# RJ_IGVC_Estop.net
KiCad netlist of a schematic drawn in EAGLE
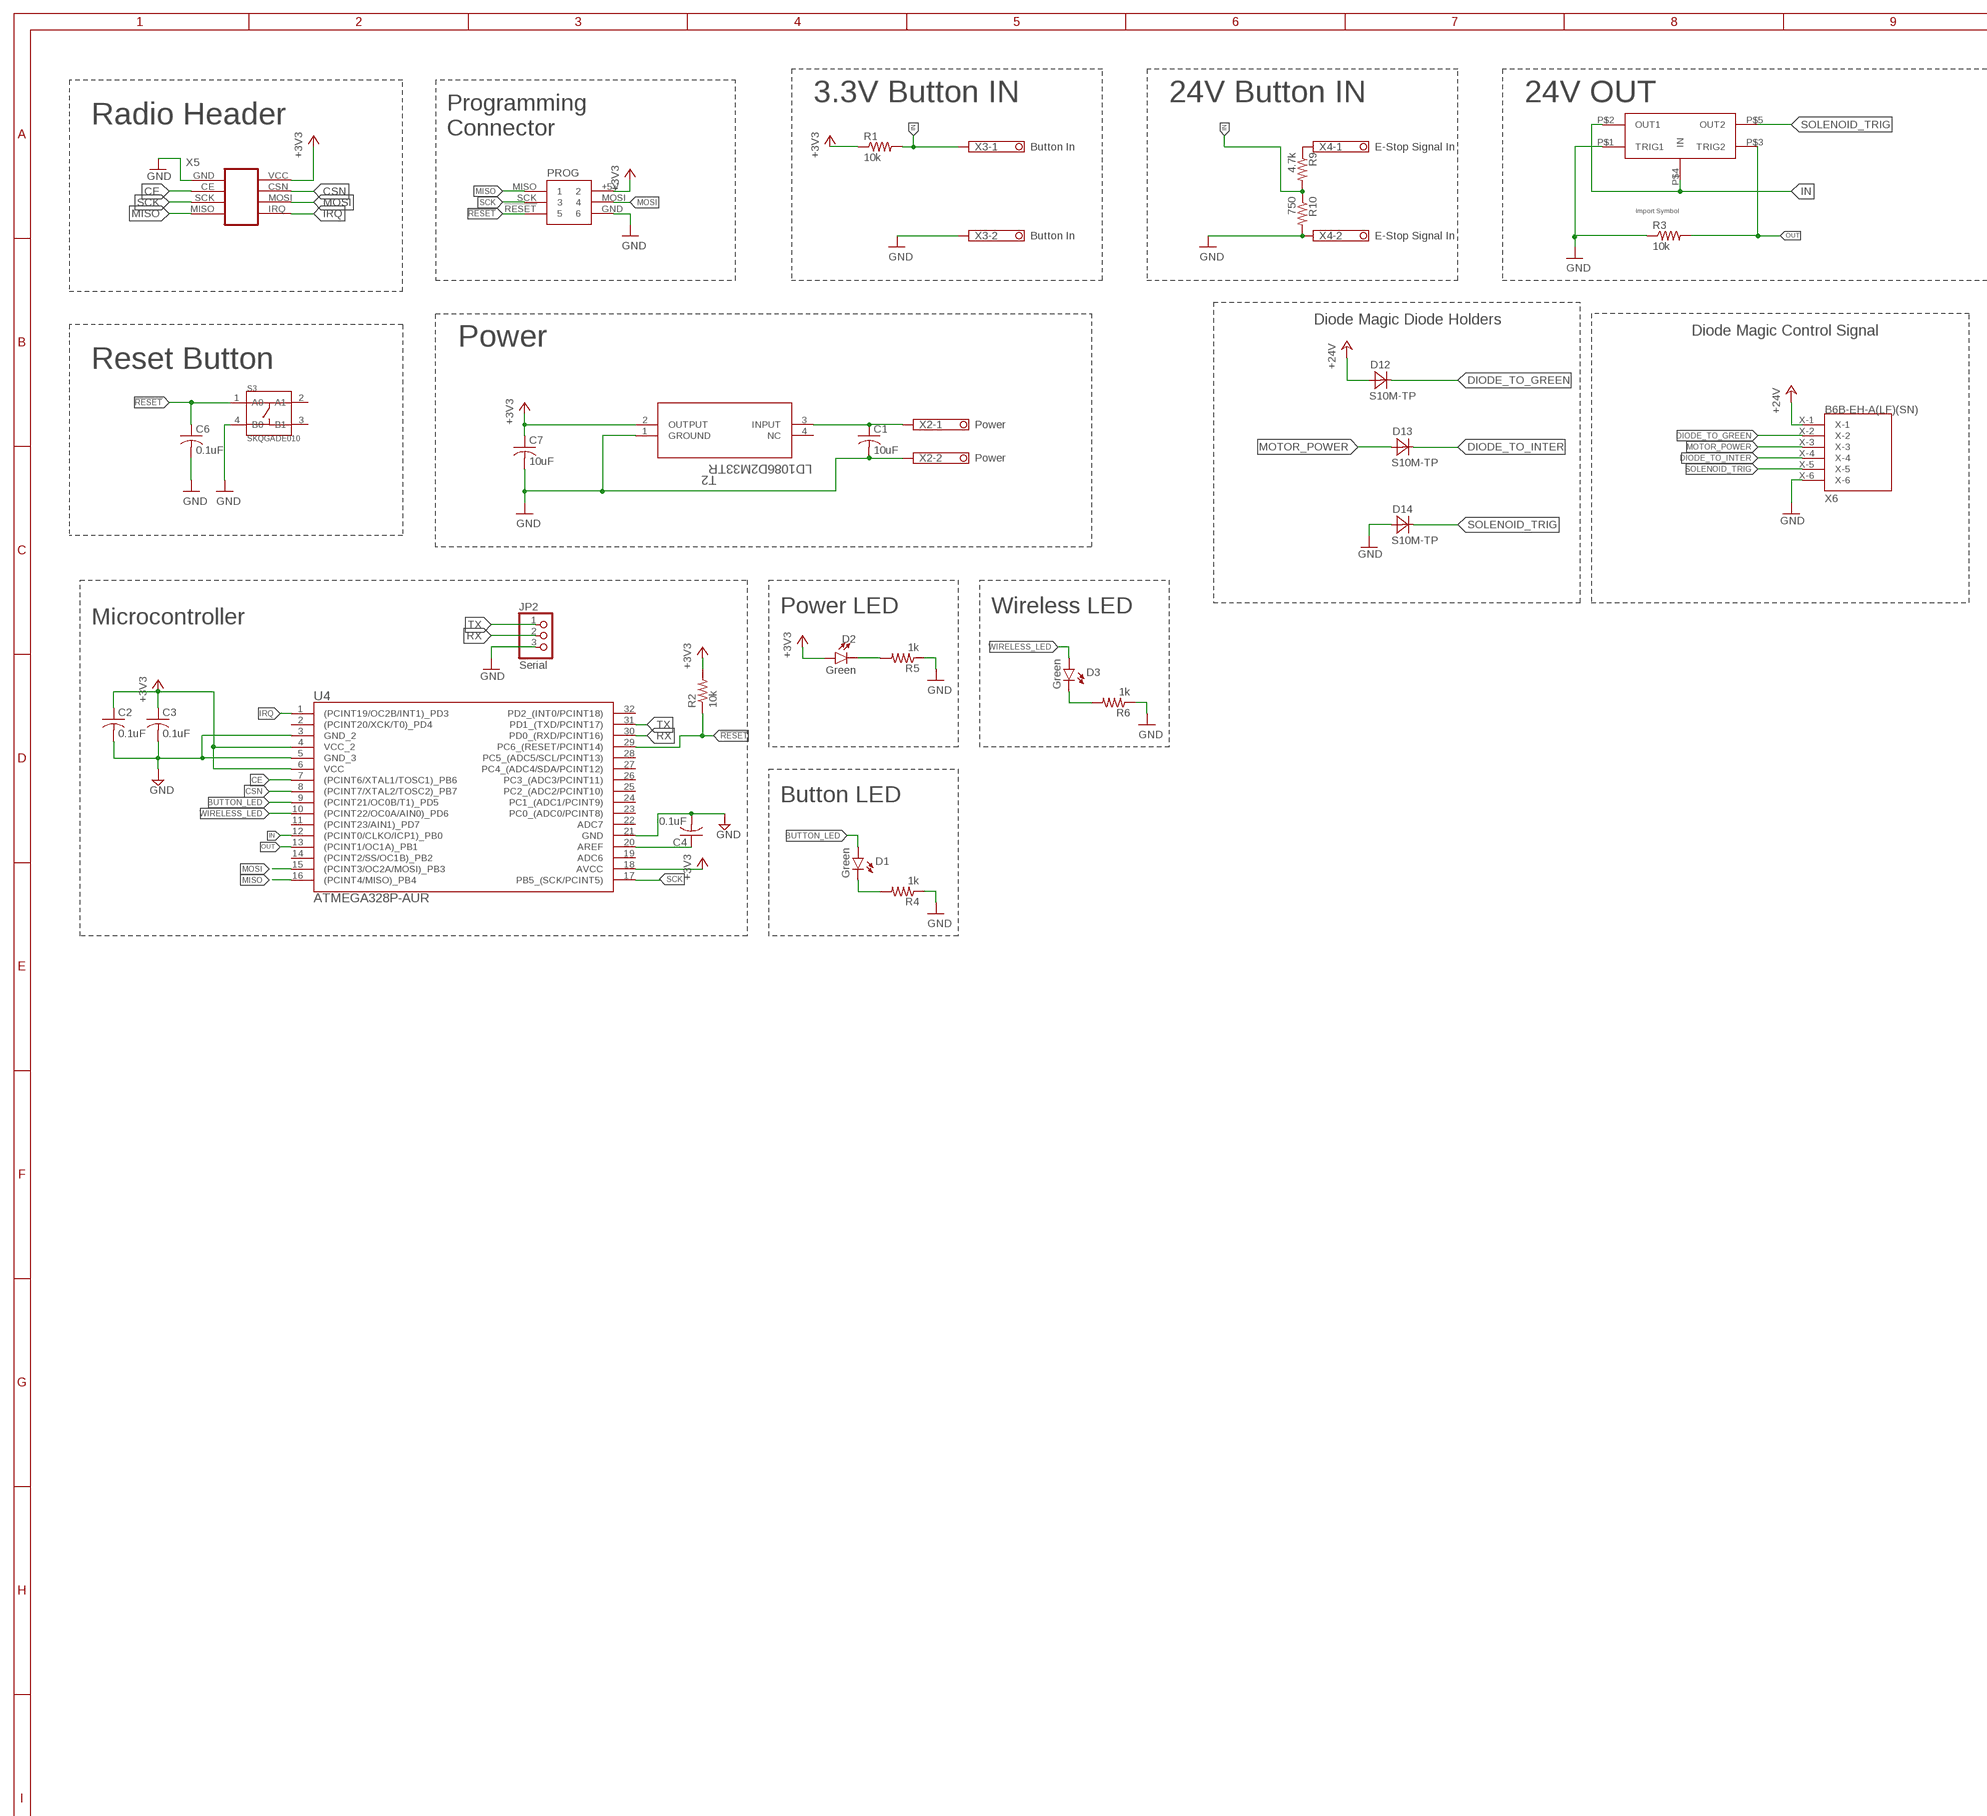
[diagram p0: schematic, sheet 1, part 1 of 2]
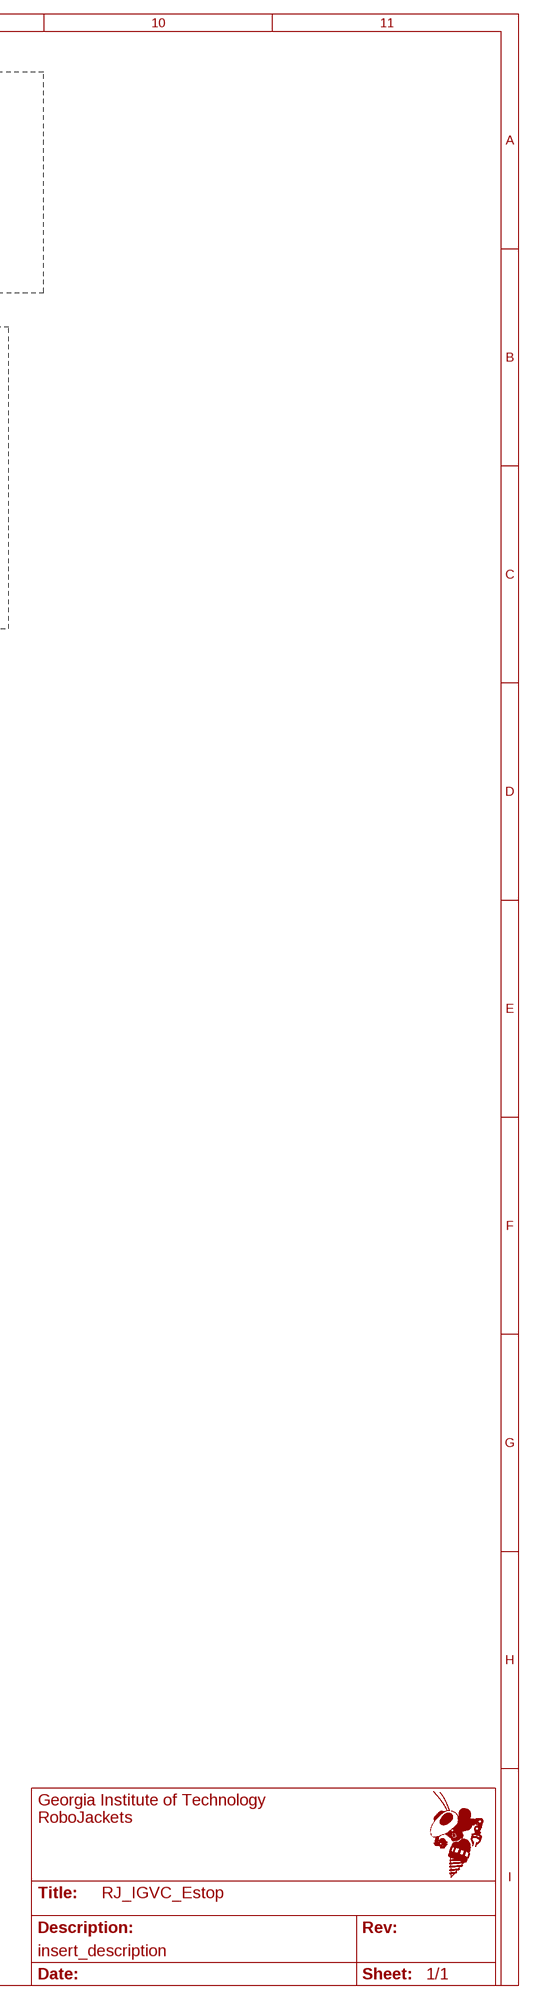
[diagram p1: schematic, sheet 1, part 2 of 2]

(export (version "E")
  (design (tool "Eeschema 10.0.6"))
  (components
    (comp (ref "C1")
      (value "10uF")
      (footprint "eagle-import:C1206")
      (libsource (lib "eagle-import") (part "C-USC1206"))
    )
    (comp (ref "C2")
      (value "0.1uF")
      (footprint "eagle-import:C0603")
      (libsource (lib "eagle-import") (part "C-USC0603"))
    )
    (comp (ref "C3")
      (value "0.1uF")
      (footprint "eagle-import:C0603")
      (libsource (lib "eagle-import") (part "C-USC0603"))
    )
    (comp (ref "C4")
      (value "0.1uF")
      (footprint "eagle-import:C0603")
      (libsource (lib "eagle-import") (part "C-USC0603"))
    )
    (comp (ref "C6")
      (value "0.1uF")
      (footprint "eagle-import:C0603")
      (libsource (lib "eagle-import") (part "resistor_348_C-USC0603"))
    )
    (comp (ref "C7")
      (value "10uF")
      (footprint "eagle-import:C1206")
      (libsource (lib "eagle-import") (part "C-USC1206"))
    )
    (comp (ref "D1")
      (value "Green")
      (footprint "eagle-import:LED-0603")
      (libsource (lib "eagle-import") (part "LED-YELLOW0603"))
    )
    (comp (ref "D2")
      (value "Green")
      (footprint "eagle-import:LED-0603")
      (libsource (lib "eagle-import") (part "LED-YELLOW0603"))
    )
    (comp (ref "D3")
      (value "Green")
      (footprint "eagle-import:LED-0603")
      (libsource (lib "eagle-import") (part "LED-YELLOW0603"))
    )
    (comp (ref "D12")
      (value "S10M-TP")
      (footprint "eagle-import:SMC")
      (libsource (lib "eagle-import") (part "S10M-TP"))
    )
    (comp (ref "D13")
      (value "S10M-TP")
      (footprint "eagle-import:SMC")
      (libsource (lib "eagle-import") (part "S10M-TP"))
    )
    (comp (ref "D14")
      (value "S10M-TP")
      (footprint "eagle-import:SMC")
      (libsource (lib "eagle-import") (part "S10M-TP"))
    )
    (comp (ref "JP2")
      (value "Serial")
      (footprint "eagle-import:1X03")
      (libsource (lib "eagle-import") (part "PINHD-1X3"))
    )
    (comp (ref "PROG")
      (value "ICSP Connector")
      (footprint "eagle-import:2X3SHROUDED")
      (libsource (lib "eagle-import") (part "2X3SHROUDED"))
    )
    (comp (ref "R1")
      (value "10k")
      (footprint "eagle-import:R0603")
      (libsource (lib "eagle-import") (part "resistor_348_R-US_R0603"))
    )
    (comp (ref "R2")
      (value "10k")
      (footprint "eagle-import:R0603")
      (libsource (lib "eagle-import") (part "R-US_R0603"))
    )
    (comp (ref "R3")
      (value "10k")
      (footprint "eagle-import:R0603")
      (libsource (lib "eagle-import") (part "resistor_348_R-US_R0603"))
    )
    (comp (ref "R4")
      (value "1k")
      (footprint "eagle-import:R0603")
      (libsource (lib "eagle-import") (part "resistor_348_R-US_R0603"))
    )
    (comp (ref "R5")
      (value "1k")
      (footprint "eagle-import:R0603")
      (libsource (lib "eagle-import") (part "resistor_348_R-US_R0603"))
    )
    (comp (ref "R6")
      (value "1k")
      (footprint "eagle-import:R0603")
      (libsource (lib "eagle-import") (part "resistor_348_R-US_R0603"))
    )
    (comp (ref "R9")
      (value "4.7k")
      (footprint "eagle-import:R0603")
      (libsource (lib "eagle-import") (part "resistor_348_R-US_R0603"))
    )
    (comp (ref "R10")
      (value "750")
      (footprint "eagle-import:R0603")
      (libsource (lib "eagle-import") (part "resistor_348_R-US_R0603"))
    )
    (comp (ref "S3")
      (value "SKQGADE010")
      (footprint "eagle-import:SW4-SMD-5.2X5.2X1.5MM")
      (libsource (lib "eagle-import") (part "SMD-SWITCH-TOP-260GF(4P-D5.2MM)"))
    )
    (comp (ref "T2")
      (value "LD1086D2M33TR")
      (footprint "eagle-import:D2PAK_A")
      (libsource (lib "eagle-import") (part "LD1086D2M33TR"))
    )
    (comp (ref "U$1")
      (value "G5LE-14")
      (footprint "eagle-import:G5LE-14")
      (libsource (lib "eagle-import") (part "G5LE-14"))
    )
    (comp (ref "U4")
      (value "ATMEGA328P-AUR")
      (footprint "eagle-import:ATMEGA328P-AUR")
      (libsource (lib "eagle-import") (part "ATMEGA328P-AUR"))
    )
    (comp (ref "X2")
      (value "Power")
      (footprint "eagle-import:1751248")
      (libsource (lib "eagle-import") (part "1751248"))
    )
    (comp (ref "X3")
      (value "Button In")
      (footprint "eagle-import:1751248")
      (libsource (lib "eagle-import") (part "1751248"))
    )
    (comp (ref "X4")
      (value "E-Stop Signal In")
      (footprint "eagle-import:1751248")
      (libsource (lib "eagle-import") (part "1751248"))
    )
    (comp (ref "X5")
      (value "NRF24L01+PA+LNA")
      (footprint "eagle-import:NRF24L01+PA+LNA")
      (libsource (lib "eagle-import") (part "NRF24L01+PA+LNA"))
    )
    (comp (ref "X6")
      (value "B6B-EH-A(LF)(SN)")
      (footprint "eagle-import:B6BEHALFSN")
      (libsource (lib "eagle-import") (part "B6B-EH-A(LF)(SN)"))
    )
  )
  (nets
    (net (code "1") (name "+3V3") (class "Default")
      (node (ref "C2") (pin "1") (pinfunction "1_1") (pintype "passive"))
      (node (ref "C3") (pin "1") (pinfunction "1_1") (pintype "passive"))
      (node (ref "C7") (pin "1") (pinfunction "1_1") (pintype "passive"))
      (node (ref "D2") (pin "A") (pinfunction "A_A") (pintype "passive"))
      (node (ref "PROG") (pin "+5V") (pinfunction "2_+5V") (pintype "bidirectional"))
      (node (ref "R1") (pin "1") (pinfunction "1_1") (pintype "passive"))
      (node (ref "R2") (pin "2") (pinfunction "2_2") (pintype "passive"))
      (node (ref "T2") (pin "2") (pinfunction "OUTPUT_2") (pintype "passive"))
      (node (ref "U4") (pin "18") (pinfunction "AVCC_18") (pintype "bidirectional"))
      (node (ref "U4") (pin "4") (pinfunction "VCC_2_4") (pintype "bidirectional"))
      (node (ref "U4") (pin "6") (pinfunction "VCC_6") (pintype "bidirectional"))
      (node (ref "X5") (pin "VCC") (pinfunction "VCC_VCC") (pintype "power_in"))
    )
    (net (code "2") (name "+24V") (class "Default")
      (node (ref "D12") (pin "A") (pinfunction "A_A") (pintype "passive"))
      (node (ref "X6") (pin "X-1") (pinfunction "X-1_X-1") (pintype "bidirectional"))
    )
    (net (code "3") (name "/~{RESET}") (class "Default")
      (node (ref "C6") (pin "1") (pinfunction "1_1") (pintype "passive"))
      (node (ref "PROG") (pin "!RESET") (pinfunction "5_!RESET") (pintype "bidirectional"))
      (node (ref "R2") (pin "1") (pinfunction "1_1") (pintype "passive"))
      (node (ref "S3") (pin "1") (pinfunction "A0_1") (pintype "bidirectional"))
      (node (ref "U4") (pin "29") (pinfunction "PC6_(RESET/PCINT14)_29") (pintype "bidirectional"))
    )
    (net (code "4") (name "BUTTON_LED") (class "Default")
      (node (ref "D1") (pin "A") (pinfunction "A_A") (pintype "passive"))
      (node (ref "U4") (pin "9") (pinfunction "(PCINT21/OC0B/T1)_PD5_9") (pintype "bidirectional"))
    )
    (net (code "5") (name "CE") (class "Default")
      (node (ref "U4") (pin "7") (pinfunction "(PCINT6/XTAL1/TOSC1)_PB6_7") (pintype "bidirectional"))
      (node (ref "X5") (pin "CE") (pinfunction "CE_CE") (pintype "passive"))
    )
    (net (code "6") (name "CSN") (class "Default")
      (node (ref "U4") (pin "8") (pinfunction "(PCINT7/XTAL2/TOSC2)_PB7_8") (pintype "bidirectional"))
      (node (ref "X5") (pin "CSN") (pinfunction "CSN_CSN") (pintype "passive"))
    )
    (net (code "7") (name "DIODE_TO_GREEN") (class "Default")
      (node (ref "D12") (pin "C") (pinfunction "C_C") (pintype "passive"))
      (node (ref "X6") (pin "X-2") (pinfunction "X-2_X-2") (pintype "bidirectional"))
    )
    (net (code "8") (name "DIODE_TO_INTER") (class "Default")
      (node (ref "D13") (pin "C") (pinfunction "C_C") (pintype "passive"))
      (node (ref "X6") (pin "X-4") (pinfunction "X-4_X-4") (pintype "bidirectional"))
    )
    (net (code "9") (name "GND") (class "Default")
      (node (ref "C1") (pin "2") (pinfunction "2_2") (pintype "passive"))
      (node (ref "C2") (pin "2") (pinfunction "2_2") (pintype "passive"))
      (node (ref "C3") (pin "2") (pinfunction "2_2") (pintype "passive"))
      (node (ref "C4") (pin "2") (pinfunction "2_2") (pintype "passive"))
      (node (ref "C6") (pin "2") (pinfunction "2_2") (pintype "passive"))
      (node (ref "C7") (pin "2") (pinfunction "2_2") (pintype "passive"))
      (node (ref "D14") (pin "A") (pinfunction "A_A") (pintype "passive"))
      (node (ref "JP2") (pin "3") (pinfunction "3_3") (pintype "passive"))
      (node (ref "PROG") (pin "GND") (pinfunction "6_GND") (pintype "bidirectional"))
      (node (ref "R10") (pin "2") (pinfunction "2_2") (pintype "passive"))
      (node (ref "R3") (pin "1") (pinfunction "1_1") (pintype "passive"))
      (node (ref "R4") (pin "1") (pinfunction "1_1") (pintype "passive"))
      (node (ref "R5") (pin "1") (pinfunction "1_1") (pintype "passive"))
      (node (ref "R6") (pin "1") (pinfunction "1_1") (pintype "passive"))
      (node (ref "S3") (pin "4") (pinfunction "B0_4") (pintype "bidirectional"))
      (node (ref "T2") (pin "1") (pinfunction "GROUND_1") (pintype "passive"))
      (node (ref "U$1") (pin "P$1") (pinfunction "TRIG1_P$1") (pintype "bidirectional"))
      (node (ref "U4") (pin "21") (pinfunction "GND_21") (pintype "bidirectional"))
      (node (ref "U4") (pin "3") (pinfunction "GND_2_3") (pintype "bidirectional"))
      (node (ref "U4") (pin "5") (pinfunction "GND_3_5") (pintype "bidirectional"))
      (node (ref "X2") (pin "2") (pinfunction "K_2") (pintype "passive"))
      (node (ref "X3") (pin "2") (pinfunction "K_2") (pintype "passive"))
      (node (ref "X4") (pin "2") (pinfunction "K_2") (pintype "passive"))
      (node (ref "X5") (pin "GND") (pinfunction "GND_GND") (pintype "power_in"))
      (node (ref "X6") (pin "X-6") (pinfunction "X-6_X-6") (pintype "bidirectional"))
    )
    (net (code "10") (name "IN") (class "Default")
      (node (ref "R1") (pin "2") (pinfunction "2_2") (pintype "passive"))
      (node (ref "R10") (pin "1") (pinfunction "1_1") (pintype "passive"))
      (node (ref "R9") (pin "2") (pinfunction "2_2") (pintype "passive"))
      (node (ref "U$1") (pin "P$2") (pinfunction "OUT1_P$2") (pintype "bidirectional"))
      (node (ref "U$1") (pin "P$4") (pinfunction "IN_P$4") (pintype "bidirectional"))
      (node (ref "U4") (pin "12") (pinfunction "(PCINT0/CLKO/ICP1)_PB0_12") (pintype "bidirectional"))
      (node (ref "X3") (pin "1") (pinfunction "K_1") (pintype "passive"))
    )
    (net (code "11") (name "IRQ") (class "Default")
      (node (ref "U4") (pin "1") (pinfunction "(PCINT19/OC2B/INT1)_PD3_1") (pintype "bidirectional"))
      (node (ref "X5") (pin "IRQ") (pinfunction "IRQ_IRQ") (pintype "passive"))
    )
    (net (code "12") (name "MISO") (class "Default")
      (node (ref "PROG") (pin "MISO") (pinfunction "1_MISO") (pintype "bidirectional"))
      (node (ref "U4") (pin "16") (pinfunction "(PCINT4/MISO)_PB4_16") (pintype "bidirectional"))
      (node (ref "X5") (pin "MISO") (pinfunction "MISO_MISO") (pintype "passive"))
    )
    (net (code "13") (name "MOSI") (class "Default")
      (node (ref "PROG") (pin "MOSI") (pinfunction "4_MOSI") (pintype "bidirectional"))
      (node (ref "U4") (pin "15") (pinfunction "(PCINT3/OC2A/MOSI)_PB3_15") (pintype "bidirectional"))
      (node (ref "X5") (pin "MOSI") (pinfunction "MOSI_MOSI") (pintype "passive"))
    )
    (net (code "14") (name "MOTOR_POWER") (class "Default")
      (node (ref "D13") (pin "A") (pinfunction "A_A") (pintype "passive"))
      (node (ref "X6") (pin "X-3") (pinfunction "X-3_X-3") (pintype "bidirectional"))
    )
    (net (code "15") (name "Net-(D1-PadC)") (class "Default")
      (node (ref "D1") (pin "C") (pinfunction "C_C") (pintype "passive"))
      (node (ref "R4") (pin "2") (pinfunction "2_2") (pintype "passive"))
    )
    (net (code "16") (name "Net-(D2-PadC)") (class "Default")
      (node (ref "D2") (pin "C") (pinfunction "C_C") (pintype "passive"))
      (node (ref "R5") (pin "2") (pinfunction "2_2") (pintype "passive"))
    )
    (net (code "17") (name "Net-(D3-PadC)") (class "Default")
      (node (ref "D3") (pin "C") (pinfunction "C_C") (pintype "passive"))
      (node (ref "R6") (pin "2") (pinfunction "2_2") (pintype "passive"))
    )
    (net (code "18") (name "Net-(T2-INPUT)") (class "Default")
      (node (ref "C1") (pin "1") (pinfunction "1_1") (pintype "passive"))
      (node (ref "T2") (pin "3") (pinfunction "INPUT_3") (pintype "passive"))
      (node (ref "X2") (pin "1") (pinfunction "K_1") (pintype "passive"))
    )
    (net (code "19") (name "Net-(U4-AREF)") (class "Default")
      (node (ref "C4") (pin "1") (pinfunction "1_1") (pintype "passive"))
      (node (ref "U4") (pin "20") (pinfunction "AREF_20") (pintype "bidirectional"))
    )
    (net (code "20") (name "Net-(X4A-K)") (class "Default")
      (node (ref "R9") (pin "1") (pinfunction "1_1") (pintype "passive"))
      (node (ref "X4") (pin "1") (pinfunction "K_1") (pintype "passive"))
    )
    (net (code "21") (name "OUT") (class "Default")
      (node (ref "R3") (pin "2") (pinfunction "2_2") (pintype "passive"))
      (node (ref "U$1") (pin "P$3") (pinfunction "TRIG2_P$3") (pintype "bidirectional"))
      (node (ref "U4") (pin "13") (pinfunction "(PCINT1/OC1A)_PB1_13") (pintype "bidirectional"))
    )
    (net (code "22") (name "RX") (class "Default")
      (node (ref "JP2") (pin "2") (pinfunction "2_2") (pintype "passive"))
      (node (ref "U4") (pin "30") (pinfunction "PD0_(RXD/PCINT16)_30") (pintype "bidirectional"))
    )
    (net (code "23") (name "SCK") (class "Default")
      (node (ref "PROG") (pin "SCK") (pinfunction "3_SCK") (pintype "bidirectional"))
      (node (ref "U4") (pin "17") (pinfunction "PB5_(SCK/PCINT5)_17") (pintype "bidirectional"))
      (node (ref "X5") (pin "SCK") (pinfunction "SCK_SCK") (pintype "passive"))
    )
    (net (code "24") (name "SOLENOID_TRIG") (class "Default")
      (node (ref "D14") (pin "C") (pinfunction "C_C") (pintype "passive"))
      (node (ref "U$1") (pin "P$5") (pinfunction "OUT2_P$5") (pintype "bidirectional"))
      (node (ref "X6") (pin "X-5") (pinfunction "X-5_X-5") (pintype "bidirectional"))
    )
    (net (code "25") (name "TX") (class "Default")
      (node (ref "JP2") (pin "1") (pinfunction "1_1") (pintype "passive"))
      (node (ref "U4") (pin "31") (pinfunction "PD1_(TXD/PCINT17)_31") (pintype "bidirectional"))
    )
    (net (code "26") (name "WIRELESS_LED") (class "Default")
      (node (ref "D3") (pin "A") (pinfunction "A_A") (pintype "passive"))
      (node (ref "U4") (pin "10") (pinfunction "(PCINT22/OC0A/AIN0)_PD6_10") (pintype "bidirectional"))
    )
    (net (code "27") (name "unconnected-(S3-A1-Pad2)") (class "Default")
      (node (ref "S3") (pin "2") (pinfunction "A1_2") (pintype "bidirectional"))
    )
    (net (code "28") (name "unconnected-(S3-B1-Pad3)") (class "Default")
      (node (ref "S3") (pin "3") (pinfunction "B1_3") (pintype "bidirectional"))
    )
    (net (code "29") (name "unconnected-(T2-NC-Pad4)") (class "Default")
      (node (ref "T2") (pin "4") (pinfunction "NC_4") (pintype "passive"))
    )
    (net (code "30") (name "unconnected-(U4-(PCINT2{slash}SS{slash}OC1B)_PB2-Pad14)") (class "Default")
      (node (ref "U4") (pin "14") (pinfunction "(PCINT2/SS/OC1B)_PB2_14") (pintype "bidirectional"))
    )
    (net (code "31") (name "unconnected-(U4-(PCINT20{slash}XCK{slash}T0)_PD4-Pad2)") (class "Default")
      (node (ref "U4") (pin "2") (pinfunction "(PCINT20/XCK/T0)_PD4_2") (pintype "bidirectional"))
    )
    (net (code "32") (name "unconnected-(U4-(PCINT23{slash}AIN1)_PD7-Pad11)") (class "Default")
      (node (ref "U4") (pin "11") (pinfunction "(PCINT23/AIN1)_PD7_11") (pintype "bidirectional"))
    )
    (net (code "33") (name "unconnected-(U4-ADC6-Pad19)") (class "Default")
      (node (ref "U4") (pin "19") (pinfunction "ADC6_19") (pintype "bidirectional"))
    )
    (net (code "34") (name "unconnected-(U4-ADC7-Pad22)") (class "Default")
      (node (ref "U4") (pin "22") (pinfunction "ADC7_22") (pintype "bidirectional"))
    )
    (net (code "35") (name "unconnected-(U4-PC0_(ADC0{slash}PCINT8)-Pad23)") (class "Default")
      (node (ref "U4") (pin "23") (pinfunction "PC0_(ADC0/PCINT8)_23") (pintype "bidirectional"))
    )
    (net (code "36") (name "unconnected-(U4-PC1_(ADC1{slash}PCINT9)-Pad24)") (class "Default")
      (node (ref "U4") (pin "24") (pinfunction "PC1_(ADC1/PCINT9)_24") (pintype "bidirectional"))
    )
    (net (code "37") (name "unconnected-(U4-PC2_(ADC2{slash}PCINT10)-Pad25)") (class "Default")
      (node (ref "U4") (pin "25") (pinfunction "PC2_(ADC2/PCINT10)_25") (pintype "bidirectional"))
    )
    (net (code "38") (name "unconnected-(U4-PC3_(ADC3{slash}PCINT11)-Pad26)") (class "Default")
      (node (ref "U4") (pin "26") (pinfunction "PC3_(ADC3/PCINT11)_26") (pintype "bidirectional"))
    )
    (net (code "39") (name "unconnected-(U4-PC4_(ADC4{slash}SDA{slash}PCINT12)-Pad27)") (class "Default")
      (node (ref "U4") (pin "27") (pinfunction "PC4_(ADC4/SDA/PCINT12)_27") (pintype "bidirectional"))
    )
    (net (code "40") (name "unconnected-(U4-PC5_(ADC5{slash}SCL{slash}PCINT13)-Pad28)") (class "Default")
      (node (ref "U4") (pin "28") (pinfunction "PC5_(ADC5/SCL/PCINT13)_28") (pintype "bidirectional"))
    )
    (net (code "41") (name "unconnected-(U4-PD2_(INT0{slash}PCINT18)-Pad32)") (class "Default")
      (node (ref "U4") (pin "32") (pinfunction "PD2_(INT0/PCINT18)_32") (pintype "bidirectional"))
    )
  )
)
